# P-FTINT-1-1.net
KiCad netlist of a schematic drawn in Altium Designer
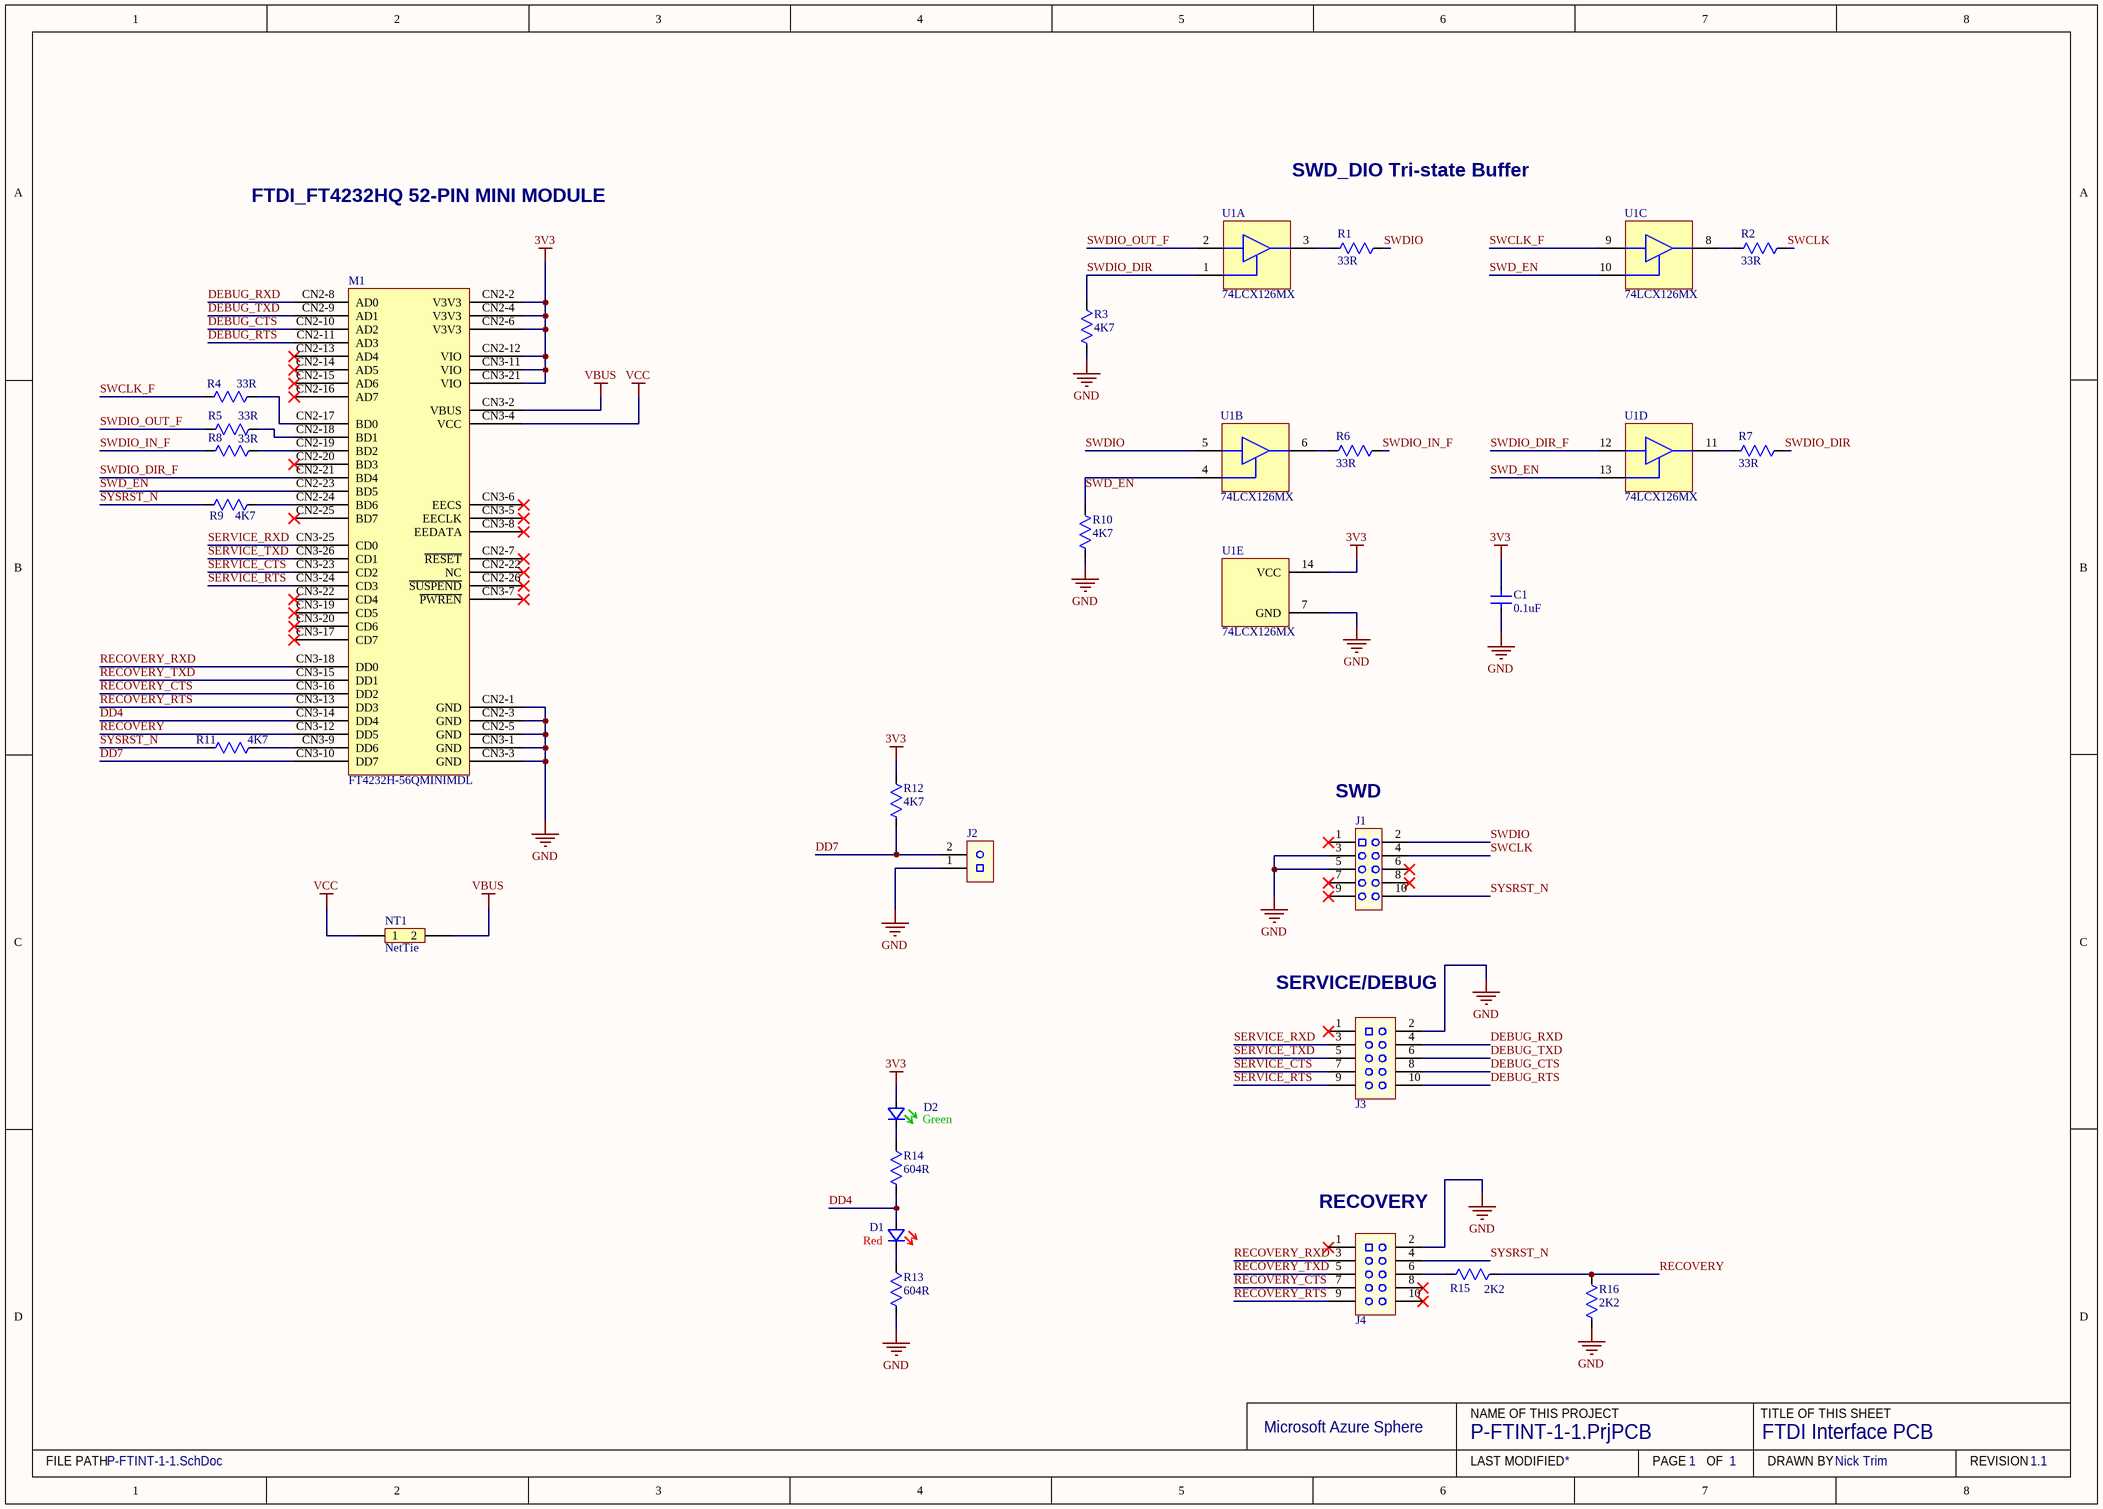
[diagram p0: P-FTINT-1-1.SchDoc]

(export (version "E")
  (design (tool "Eeschema 10.0.6"))
  (components
    (comp (ref "C1")
      (value "0.1uF")
      (footprint "CAP 0603 (1608) x 1.2mm")
      (description "CAP CER 0.1UF 25V X7R 0603")
      (fields
        (field (name "MANUFACTURER") "TDK")
        (field (name "MANUFACTURER PART NUMBER") "CGA3E2X7R1E104K080AA")
      )
      (libsource (lib "TDK-Capacitor_C_0603") (part "CGA3E2X7R1E104K080AA"))
    )
    (comp (ref "D1")
      (value "SML-D12U")
      (footprint "Rohm SML-D12 Red")
      (description "1.6 x 0.8 x 0.55mm (0603) LED 620nm Red")
      (fields
        (field (name "MANUFACTURER") "Rohm Semiconductor")
        (field (name "MANUFACTURER PART NUMBER") "SML-D12U8WT86")
        (field (name "COLOUR") "Red")
      )
      (libsource (lib "Rohm") (part "SML-D12U"))
    )
    (comp (ref "D2")
      (value "SML-D12P")
      (footprint "Rohm SML-D12 Green")
      (description "1.6 x 0.8 x 0.55mm (0603) LED 560nm Green")
      (fields
        (field (name "MANUFACTURER") "Rohm Semiconductor")
        (field (name "MANUFACTURER PART NUMBER") "SML-D12P8WT86")
        (field (name "COLOUR") "Green")
      )
      (libsource (lib "Rohm") (part "SML-D12P"))
    )
    (comp (ref "J1")
      (value "FTSH-105-01-F-DV-K")
      (footprint "SAMTEC-FTSH-105-01-X-DV-K")
      (description "CONN HEADER 10POS DUAL .05\" SMD")
      (fields (field (name "MANUFACTURER") "Samtec Inc."))
      (libsource (lib "Samtec") (part "FTSH-105-01-F-DV-K"))
    )
    (comp (ref "J2")
      (value "MOLEX-0022284020")
      (footprint "0022284020")
      (description "CONN HEADER 2POS .100 VERT TIN")
      (fields
        (field (name "MANUFACTURER") "Molex, LLC")
        (field (name "MANUFACTURER PART NUMBER") "0022284020")
      )
      (libsource (lib "Molex") (part "MOLEX-0022284020"))
    )
    (comp (ref "J3")
      (value "0901310765")
      (footprint "901310765")
      (description "CONN HEADER 10POS .100\" STR GOLD")
      (fields (field (name "MANUFACTURER") "Molex, LLC"))
      (libsource (lib "Molex") (part "MOLEX-0901310765"))
    )
    (comp (ref "J4")
      (value "0901310765")
      (footprint "901310765")
      (description "CONN HEADER 10POS .100\" STR GOLD")
      (fields (field (name "MANUFACTURER") "Molex, LLC"))
      (libsource (lib "Molex") (part "MOLEX-0901310765"))
    )
    (comp (ref "M1")
      (value "FT4232H-56QMINIMDL")
      (footprint "FT4232H-56Q")
      (description "IC MINI MODULE USB/FIFO 56QFN")
      (fields (field (name "MANUFACTURER") "FTDI"))
      (libsource (lib "FTDI") (part "FT4232H-56QMINIMDL"))
    )
    (comp (ref "NT1") (value "NetTie") (footprint "NetTie") (libsource (lib "generic") (part "NetTie")))
    (comp (ref "R1")
      (value "33R")
      (footprint "RES0603")
      (description "RES SMD 33 OHM 5% 1/10W 0603")
      (fields
        (field (name "MANUFACTURER") "Panasonic")
        (field (name "MANUFACTURER PART NUMBER") "ERJ-3GEYJ330V")
      )
      (libsource (lib "Panasonic_Resistor_ERJ3GR_0603") (part "ERJ-3GEYJ330V"))
    )
    (comp (ref "R2")
      (value "33R")
      (footprint "RES0603")
      (description "RES SMD 33 OHM 5% 1/10W 0603")
      (fields
        (field (name "MANUFACTURER") "Panasonic")
        (field (name "MANUFACTURER PART NUMBER") "ERJ-3GEYJ330V")
      )
      (libsource (lib "Panasonic_Resistor_ERJ3GR_0603") (part "ERJ-3GEYJ330V"))
    )
    (comp (ref "R3")
      (value "4K7")
      (footprint "RES0603")
      (description "RES SMD 4.7K OHM 5% 1/10W 0603")
      (fields
        (field (name "MANUFACTURER") "Panasonic")
        (field (name "MANUFACTURER PART NUMBER") "ERJ-3GEYJ472V")
      )
      (libsource (lib "Panasonic_Resistor_ERJ3GR_0603") (part "ERJ-3GEYJ472V"))
    )
    (comp (ref "R4")
      (value "33R")
      (footprint "RES0603")
      (description "RES SMD 33 OHM 5% 1/10W 0603")
      (fields
        (field (name "MANUFACTURER") "Panasonic")
        (field (name "MANUFACTURER PART NUMBER") "ERJ-3GEYJ330V")
      )
      (libsource (lib "Panasonic_Resistor_ERJ3GR_0603") (part "ERJ-3GEYJ330V"))
    )
    (comp (ref "R5")
      (value "33R")
      (footprint "RES0603")
      (description "RES SMD 33 OHM 5% 1/10W 0603")
      (fields
        (field (name "MANUFACTURER") "Panasonic")
        (field (name "MANUFACTURER PART NUMBER") "ERJ-3GEYJ330V")
      )
      (libsource (lib "Panasonic_Resistor_ERJ3GR_0603") (part "ERJ-3GEYJ330V"))
    )
    (comp (ref "R6")
      (value "33R")
      (footprint "RES0603")
      (description "RES SMD 33 OHM 5% 1/10W 0603")
      (fields
        (field (name "MANUFACTURER") "Panasonic")
        (field (name "MANUFACTURER PART NUMBER") "ERJ-3GEYJ330V")
      )
      (libsource (lib "Panasonic_Resistor_ERJ3GR_0603") (part "ERJ-3GEYJ330V"))
    )
    (comp (ref "R7")
      (value "33R")
      (footprint "RES0603")
      (description "RES SMD 33 OHM 5% 1/10W 0603")
      (fields
        (field (name "MANUFACTURER") "Panasonic")
        (field (name "MANUFACTURER PART NUMBER") "ERJ-3GEYJ330V")
      )
      (libsource (lib "Panasonic_Resistor_ERJ3GR_0603") (part "ERJ-3GEYJ330V"))
    )
    (comp (ref "R8")
      (value "33R")
      (footprint "RES0603")
      (description "RES SMD 33 OHM 5% 1/10W 0603")
      (fields
        (field (name "MANUFACTURER") "Panasonic")
        (field (name "MANUFACTURER PART NUMBER") "ERJ-3GEYJ330V")
      )
      (libsource (lib "Panasonic_Resistor_ERJ3GR_0603") (part "ERJ-3GEYJ330V"))
    )
    (comp (ref "R9")
      (value "4K7")
      (footprint "RES0603")
      (description "RES SMD 4.7K OHM 5% 1/10W 0603")
      (fields
        (field (name "MANUFACTURER") "Panasonic")
        (field (name "MANUFACTURER PART NUMBER") "ERJ-3GEYJ472V")
      )
      (libsource (lib "Panasonic_Resistor_ERJ3GR_0603") (part "ERJ-3GEYJ472V"))
    )
    (comp (ref "R10")
      (value "4K7")
      (footprint "RES0603")
      (description "RES SMD 4.7K OHM 5% 1/10W 0603")
      (fields
        (field (name "MANUFACTURER") "Panasonic")
        (field (name "MANUFACTURER PART NUMBER") "ERJ-3GEYJ472V")
      )
      (libsource (lib "Panasonic_Resistor_ERJ3GR_0603") (part "ERJ-3GEYJ472V"))
    )
    (comp (ref "R11")
      (value "4K7")
      (footprint "RES0603")
      (description "RES SMD 4.7K OHM 5% 1/10W 0603")
      (fields
        (field (name "MANUFACTURER") "Panasonic")
        (field (name "MANUFACTURER PART NUMBER") "ERJ-3GEYJ472V")
      )
      (libsource (lib "Panasonic_Resistor_ERJ3GR_0603") (part "ERJ-3GEYJ472V"))
    )
    (comp (ref "R12")
      (value "4K7")
      (footprint "RES0603")
      (description "RES SMD 4.7K OHM 5% 1/10W 0603")
      (fields
        (field (name "MANUFACTURER") "Panasonic")
        (field (name "MANUFACTURER PART NUMBER") "ERJ-3GEYJ472V")
      )
      (libsource (lib "Panasonic_Resistor_ERJ3GR_0603") (part "ERJ-3GEYJ472V"))
    )
    (comp (ref "R13")
      (value "604R")
      (footprint "RES0603")
      (description "RES SMD 604 OHM 1% 1/10W 0603")
      (fields
        (field (name "MANUFACTURER") "Panasonic")
        (field (name "MANUFACTURER PART NUMBER") "ERJ-3EKF6040V")
      )
      (libsource (lib "Panasonic_Resistor_ERJ3GR_0603") (part "ERJ-3EKF6040V"))
    )
    (comp (ref "R14")
      (value "604R")
      (footprint "RES0603")
      (description "RES SMD 604 OHM 1% 1/10W 0603")
      (fields
        (field (name "MANUFACTURER") "Panasonic")
        (field (name "MANUFACTURER PART NUMBER") "ERJ-3EKF6040V")
      )
      (libsource (lib "Panasonic_Resistor_ERJ3GR_0603") (part "ERJ-3EKF6040V"))
    )
    (comp (ref "R15")
      (value "2K2")
      (footprint "RES0603")
      (description "RES SMD 2.2K OHM 5% 1/10W 0603")
      (fields
        (field (name "MANUFACTURER") "Panasonic")
        (field (name "MANUFACTURER PART NUMBER") "ERJ-3GEYJ222V")
      )
      (libsource (lib "Panasonic_Resistor_ERJ3GR_0603") (part "ERJ-3GEYJ222V"))
    )
    (comp (ref "R16")
      (value "2K2")
      (footprint "RES0603")
      (description "RES SMD 2.2K OHM 5% 1/10W 0603")
      (fields
        (field (name "MANUFACTURER") "Panasonic")
        (field (name "MANUFACTURER PART NUMBER") "ERJ-3GEYJ222V")
      )
      (libsource (lib "Panasonic_Resistor_ERJ3GR_0603") (part "ERJ-3GEYJ222V"))
    )
    (comp (ref "U1")
      (value "74LCX126MX")
      (footprint "74LCX126MX")
      (description "Buffers & Line Drivers LV Quad Buffer 5V Tolerant I/O")
      (fields (field (name "MANUFACTURER") "ON Semiconductor / Fairchild"))
      (libsource (lib "OnSemiconductor") (part "74LCX126MX"))
    )
  )
  (nets
    (net (code "1") (name "/DD4") (class "Default")
      (node (ref "D1") (pin "2") (pinfunction "A_2") (pintype "passive"))
      (node (ref "M1") (pin "CN3-14") (pinfunction "DD4_CN3-14") (pintype "passive"))
      (node (ref "R14") (pin "2") (pinfunction "2_2") (pintype "passive"))
    )
    (net (code "2") (name "/DD7") (class "Default")
      (node (ref "J2") (pin "2") (pinfunction "2_2") (pintype "passive"))
      (node (ref "M1") (pin "CN3-10") (pinfunction "DD7_CN3-10") (pintype "passive"))
      (node (ref "R12") (pin "2") (pinfunction "2_2") (pintype "passive"))
    )
    (net (code "3") (name "/DEBUG_CTS") (class "Default")
      (node (ref "J3") (pin "8") (pinfunction "8_8") (pintype "passive"))
      (node (ref "M1") (pin "CN2-10") (pinfunction "AD2_CN2-10") (pintype "passive"))
    )
    (net (code "4") (name "/DEBUG_RTS") (class "Default")
      (node (ref "J3") (pin "10") (pinfunction "10_10") (pintype "passive"))
      (node (ref "M1") (pin "CN2-11") (pinfunction "AD3_CN2-11") (pintype "passive"))
    )
    (net (code "5") (name "/DEBUG_RXD") (class "Default")
      (node (ref "J3") (pin "4") (pinfunction "4_4") (pintype "passive"))
      (node (ref "M1") (pin "CN2-8") (pinfunction "AD0_CN2-8") (pintype "passive"))
    )
    (net (code "6") (name "/DEBUG_TXD") (class "Default")
      (node (ref "J3") (pin "6") (pinfunction "6_6") (pintype "passive"))
      (node (ref "M1") (pin "CN2-9") (pinfunction "AD1_CN2-9") (pintype "passive"))
    )
    (net (code "7") (name "/RECOVERY") (class "Default")
      (node (ref "M1") (pin "CN3-12") (pinfunction "DD5_CN3-12") (pintype "passive"))
      (node (ref "R15") (pin "1") (pinfunction "1_1") (pintype "passive"))
      (node (ref "R16") (pin "1") (pinfunction "1_1") (pintype "passive"))
    )
    (net (code "8") (name "/RECOVERY_CTS") (class "Default")
      (node (ref "J4") (pin "7") (pinfunction "7_7") (pintype "passive"))
      (node (ref "M1") (pin "CN3-16") (pinfunction "DD2_CN3-16") (pintype "passive"))
    )
    (net (code "9") (name "/RECOVERY_RTS") (class "Default")
      (node (ref "J4") (pin "9") (pinfunction "9_9") (pintype "passive"))
      (node (ref "M1") (pin "CN3-13") (pinfunction "DD3_CN3-13") (pintype "passive"))
    )
    (net (code "10") (name "/RECOVERY_RXD") (class "Default")
      (node (ref "J4") (pin "3") (pinfunction "3_3") (pintype "passive"))
      (node (ref "M1") (pin "CN3-18") (pinfunction "DD0_CN3-18") (pintype "passive"))
    )
    (net (code "11") (name "/RECOVERY_TXD") (class "Default")
      (node (ref "J4") (pin "5") (pinfunction "5_5") (pintype "passive"))
      (node (ref "M1") (pin "CN3-15") (pinfunction "DD1_CN3-15") (pintype "passive"))
    )
    (net (code "12") (name "/SERVICE_CTS") (class "Default")
      (node (ref "J3") (pin "7") (pinfunction "7_7") (pintype "passive"))
      (node (ref "M1") (pin "CN3-23") (pinfunction "CD2_CN3-23") (pintype "passive"))
    )
    (net (code "13") (name "/SERVICE_RTS") (class "Default")
      (node (ref "J3") (pin "9") (pinfunction "9_9") (pintype "passive"))
      (node (ref "M1") (pin "CN3-24") (pinfunction "CD3_CN3-24") (pintype "passive"))
    )
    (net (code "14") (name "/SERVICE_RXD") (class "Default")
      (node (ref "J3") (pin "3") (pinfunction "3_3") (pintype "passive"))
      (node (ref "M1") (pin "CN3-25") (pinfunction "CD0_CN3-25") (pintype "passive"))
    )
    (net (code "15") (name "/SERVICE_TXD") (class "Default")
      (node (ref "J3") (pin "5") (pinfunction "5_5") (pintype "passive"))
      (node (ref "M1") (pin "CN3-26") (pinfunction "CD1_CN3-26") (pintype "passive"))
    )
    (net (code "16") (name "/SWCLK") (class "Default")
      (node (ref "J1") (pin "4") (pinfunction "4_4") (pintype "passive"))
      (node (ref "R2") (pin "1") (pinfunction "1_1") (pintype "passive"))
    )
    (net (code "17") (name "/SWCLK_F") (class "Default")
      (node (ref "R4") (pin "2") (pinfunction "2_2") (pintype "passive"))
      (node (ref "U1") (pin "9") (pinfunction "3A_9") (pintype "passive"))
    )
    (net (code "18") (name "/SWDIO") (class "Default")
      (node (ref "J1") (pin "2") (pinfunction "2_2") (pintype "passive"))
      (node (ref "R1") (pin "1") (pinfunction "1_1") (pintype "passive"))
      (node (ref "U1") (pin "5") (pinfunction "2A_5") (pintype "passive"))
    )
    (net (code "19") (name "/SWDIO_DIR") (class "Default")
      (node (ref "R3") (pin "1") (pinfunction "1_1") (pintype "passive"))
      (node (ref "R7") (pin "1") (pinfunction "1_1") (pintype "passive"))
      (node (ref "U1") (pin "1") (pinfunction "1OE_1") (pintype "passive"))
    )
    (net (code "20") (name "/SWDIO_DIR_F") (class "Default")
      (node (ref "M1") (pin "CN2-21") (pinfunction "BD4_CN2-21") (pintype "passive"))
      (node (ref "U1") (pin "12") (pinfunction "4A_12") (pintype "passive"))
    )
    (net (code "21") (name "/SWDIO_IN_F") (class "Default")
      (node (ref "R6") (pin "1") (pinfunction "1_1") (pintype "passive"))
      (node (ref "R8") (pin "2") (pinfunction "2_2") (pintype "passive"))
    )
    (net (code "22") (name "/SWDIO_OUT_F") (class "Default")
      (node (ref "R5") (pin "2") (pinfunction "2_2") (pintype "passive"))
      (node (ref "U1") (pin "2") (pinfunction "1A_2") (pintype "passive"))
    )
    (net (code "23") (name "/SWD_EN") (class "Default")
      (node (ref "M1") (pin "CN2-23") (pinfunction "BD5_CN2-23") (pintype "passive"))
      (node (ref "R10") (pin "1") (pinfunction "1_1") (pintype "passive"))
      (node (ref "U1") (pin "10") (pinfunction "3OE_10") (pintype "passive"))
      (node (ref "U1") (pin "13") (pinfunction "4OE_13") (pintype "passive"))
      (node (ref "U1") (pin "4") (pinfunction "2OE_4") (pintype "passive"))
    )
    (net (code "24") (name "/SYSRST_N") (class "Default")
      (node (ref "J1") (pin "10") (pinfunction "10_10") (pintype "passive"))
      (node (ref "J4") (pin "4") (pinfunction "4_4") (pintype "passive"))
      (node (ref "R11") (pin "2") (pinfunction "2_2") (pintype "passive"))
      (node (ref "R9") (pin "2") (pinfunction "2_2") (pintype "passive"))
    )
    (net (code "25") (name "3V3") (class "Default")
      (node (ref "C1") (pin "2") (pinfunction "2_2") (pintype "passive"))
      (node (ref "D2") (pin "2") (pinfunction "A_2") (pintype "passive"))
      (node (ref "M1") (pin "CN2-12") (pinfunction "VIO_CN2-12") (pintype "passive"))
      (node (ref "M1") (pin "CN2-2") (pinfunction "V3V3_CN2-2") (pintype "passive"))
      (node (ref "M1") (pin "CN2-4") (pinfunction "V3V3_CN2-4") (pintype "passive"))
      (node (ref "M1") (pin "CN2-6") (pinfunction "V3V3_CN2-6") (pintype "passive"))
      (node (ref "M1") (pin "CN3-11") (pinfunction "VIO_CN3-11") (pintype "passive"))
      (node (ref "M1") (pin "CN3-21") (pinfunction "VIO_CN3-21") (pintype "passive"))
      (node (ref "R12") (pin "1") (pinfunction "1_1") (pintype "passive"))
      (node (ref "U1") (pin "14") (pinfunction "VCC_14") (pintype "passive"))
    )
    (net (code "26") (name "GND") (class "Default")
      (node (ref "C1") (pin "1") (pinfunction "1_1") (pintype "passive"))
      (node (ref "J1") (pin "3") (pinfunction "3_3") (pintype "passive"))
      (node (ref "J1") (pin "5") (pinfunction "5_5") (pintype "passive"))
      (node (ref "J2") (pin "1") (pinfunction "1_1") (pintype "passive"))
      (node (ref "J3") (pin "2") (pinfunction "2_2") (pintype "passive"))
      (node (ref "J4") (pin "2") (pinfunction "2_2") (pintype "passive"))
      (node (ref "M1") (pin "CN2-1") (pinfunction "GND_CN2-1") (pintype "passive"))
      (node (ref "M1") (pin "CN2-3") (pinfunction "GND_CN2-3") (pintype "passive"))
      (node (ref "M1") (pin "CN2-5") (pinfunction "GND_CN2-5") (pintype "passive"))
      (node (ref "M1") (pin "CN3-1") (pinfunction "GND_CN3-1") (pintype "passive"))
      (node (ref "M1") (pin "CN3-3") (pinfunction "GND_CN3-3") (pintype "passive"))
      (node (ref "R10") (pin "2") (pinfunction "2_2") (pintype "passive"))
      (node (ref "R13") (pin "2") (pinfunction "2_2") (pintype "passive"))
      (node (ref "R16") (pin "2") (pinfunction "2_2") (pintype "passive"))
      (node (ref "R3") (pin "2") (pinfunction "2_2") (pintype "passive"))
      (node (ref "U1") (pin "7") (pinfunction "GND_7") (pintype "power_in"))
    )
    (net (code "27") (name "Net-(D1-K)") (class "Default")
      (node (ref "D1") (pin "1") (pinfunction "K_1") (pintype "passive"))
      (node (ref "R13") (pin "1") (pinfunction "1_1") (pintype "passive"))
    )
    (net (code "28") (name "Net-(D2-K)") (class "Default")
      (node (ref "D2") (pin "1") (pinfunction "K_1") (pintype "passive"))
      (node (ref "R14") (pin "1") (pinfunction "1_1") (pintype "passive"))
    )
    (net (code "29") (name "Net-(J4-Pad6)") (class "Default")
      (node (ref "J4") (pin "6") (pinfunction "6_6") (pintype "passive"))
      (node (ref "R15") (pin "2") (pinfunction "2_2") (pintype "passive"))
    )
    (net (code "30") (name "Net-(M1-BD0)") (class "Default")
      (node (ref "M1") (pin "CN2-17") (pinfunction "BD0_CN2-17") (pintype "passive"))
      (node (ref "R4") (pin "1") (pinfunction "1_1") (pintype "passive"))
    )
    (net (code "31") (name "Net-(M1-BD1)") (class "Default")
      (node (ref "M1") (pin "CN2-18") (pinfunction "BD1_CN2-18") (pintype "passive"))
      (node (ref "R5") (pin "1") (pinfunction "1_1") (pintype "passive"))
    )
    (net (code "32") (name "Net-(M1-BD2)") (class "Default")
      (node (ref "M1") (pin "CN2-19") (pinfunction "BD2_CN2-19") (pintype "passive"))
      (node (ref "R8") (pin "1") (pinfunction "1_1") (pintype "passive"))
    )
    (net (code "33") (name "Net-(M1-BD6)") (class "Default")
      (node (ref "M1") (pin "CN2-24") (pinfunction "BD6_CN2-24") (pintype "passive"))
      (node (ref "R9") (pin "1") (pinfunction "1_1") (pintype "passive"))
    )
    (net (code "34") (name "Net-(M1-DD6)") (class "Default")
      (node (ref "M1") (pin "CN3-9") (pinfunction "DD6_CN3-9") (pintype "passive"))
      (node (ref "R11") (pin "1") (pinfunction "1_1") (pintype "passive"))
    )
    (net (code "35") (name "Net-(U1A-1Y)") (class "Default")
      (node (ref "R1") (pin "2") (pinfunction "2_2") (pintype "passive"))
      (node (ref "U1") (pin "3") (pinfunction "1Y_3") (pintype "passive"))
    )
    (net (code "36") (name "Net-(U1B-2Y)") (class "Default")
      (node (ref "R6") (pin "2") (pinfunction "2_2") (pintype "passive"))
      (node (ref "U1") (pin "6") (pinfunction "2Y_6") (pintype "passive"))
    )
    (net (code "37") (name "Net-(U1C-3Y)") (class "Default")
      (node (ref "R2") (pin "2") (pinfunction "2_2") (pintype "passive"))
      (node (ref "U1") (pin "8") (pinfunction "3Y_8") (pintype "passive"))
    )
    (net (code "38") (name "Net-(U1D-4Y)") (class "Default")
      (node (ref "R7") (pin "2") (pinfunction "2_2") (pintype "passive"))
      (node (ref "U1") (pin "11") (pinfunction "4Y_11") (pintype "passive"))
    )
    (net (code "39") (name "VBUS") (class "Default")
      (node (ref "M1") (pin "CN3-2") (pinfunction "VBUS_CN3-2") (pintype "passive"))
      (node (ref "NT1") (pin "2") (pinfunction "2_2") (pintype "passive"))
    )
    (net (code "40") (name "VCC") (class "Default")
      (node (ref "M1") (pin "CN3-4") (pinfunction "VCC_CN3-4") (pintype "passive"))
      (node (ref "NT1") (pin "1") (pinfunction "1_1") (pintype "passive"))
    )
    (net (code "41") (name "unconnected-(J1-Pad1)") (class "Default")
      (node (ref "J1") (pin "1") (pinfunction "1_1") (pintype "passive+no_connect"))
    )
    (net (code "42") (name "unconnected-(J1-Pad6)") (class "Default")
      (node (ref "J1") (pin "6") (pinfunction "6_6") (pintype "passive+no_connect"))
    )
    (net (code "43") (name "unconnected-(J1-Pad7)") (class "Default")
      (node (ref "J1") (pin "7") (pinfunction "7_7") (pintype "passive+no_connect"))
    )
    (net (code "44") (name "unconnected-(J1-Pad8)") (class "Default")
      (node (ref "J1") (pin "8") (pinfunction "8_8") (pintype "passive+no_connect"))
    )
    (net (code "45") (name "unconnected-(J1-Pad9)") (class "Default")
      (node (ref "J1") (pin "9") (pinfunction "9_9") (pintype "passive+no_connect"))
    )
    (net (code "46") (name "unconnected-(J3-Pad1)") (class "Default")
      (node (ref "J3") (pin "1") (pinfunction "1_1") (pintype "passive+no_connect"))
    )
    (net (code "47") (name "unconnected-(J4-Pad1)") (class "Default")
      (node (ref "J4") (pin "1") (pinfunction "1_1") (pintype "passive+no_connect"))
    )
    (net (code "48") (name "unconnected-(J4-Pad8)") (class "Default")
      (node (ref "J4") (pin "8") (pinfunction "8_8") (pintype "passive+no_connect"))
    )
    (net (code "49") (name "unconnected-(J4-Pad10)") (class "Default")
      (node (ref "J4") (pin "10") (pinfunction "10_10") (pintype "passive+no_connect"))
    )
    (net (code "50") (name "unconnected-(M1-AD4-PadCN2-13)") (class "Default")
      (node (ref "M1") (pin "CN2-13") (pinfunction "AD4_CN2-13") (pintype "passive+no_connect"))
    )
    (net (code "51") (name "unconnected-(M1-AD5-PadCN2-14)") (class "Default")
      (node (ref "M1") (pin "CN2-14") (pinfunction "AD5_CN2-14") (pintype "passive+no_connect"))
    )
    (net (code "52") (name "unconnected-(M1-AD6-PadCN2-15)") (class "Default")
      (node (ref "M1") (pin "CN2-15") (pinfunction "AD6_CN2-15") (pintype "passive+no_connect"))
    )
    (net (code "53") (name "unconnected-(M1-AD7-PadCN2-16)") (class "Default")
      (node (ref "M1") (pin "CN2-16") (pinfunction "AD7_CN2-16") (pintype "passive+no_connect"))
    )
    (net (code "54") (name "unconnected-(M1-BD3-PadCN2-20)") (class "Default")
      (node (ref "M1") (pin "CN2-20") (pinfunction "BD3_CN2-20") (pintype "passive+no_connect"))
    )
    (net (code "55") (name "unconnected-(M1-BD7-PadCN2-25)") (class "Default")
      (node (ref "M1") (pin "CN2-25") (pinfunction "BD7_CN2-25") (pintype "passive+no_connect"))
    )
    (net (code "56") (name "unconnected-(M1-CD4-PadCN3-22)") (class "Default")
      (node (ref "M1") (pin "CN3-22") (pinfunction "CD4_CN3-22") (pintype "passive+no_connect"))
    )
    (net (code "57") (name "unconnected-(M1-CD5-PadCN3-19)") (class "Default")
      (node (ref "M1") (pin "CN3-19") (pinfunction "CD5_CN3-19") (pintype "passive+no_connect"))
    )
    (net (code "58") (name "unconnected-(M1-CD6-PadCN3-20)") (class "Default")
      (node (ref "M1") (pin "CN3-20") (pinfunction "CD6_CN3-20") (pintype "passive+no_connect"))
    )
    (net (code "59") (name "unconnected-(M1-CD7-PadCN3-17)") (class "Default")
      (node (ref "M1") (pin "CN3-17") (pinfunction "CD7_CN3-17") (pintype "passive+no_connect"))
    )
    (net (code "60") (name "unconnected-(M1-EECLK-PadCN3-5)") (class "Default")
      (node (ref "M1") (pin "CN3-5") (pinfunction "EECLK_CN3-5") (pintype "passive+no_connect"))
    )
    (net (code "61") (name "unconnected-(M1-EECS-PadCN3-6)") (class "Default")
      (node (ref "M1") (pin "CN3-6") (pinfunction "EECS_CN3-6") (pintype "passive+no_connect"))
    )
    (net (code "62") (name "unconnected-(M1-EEDATA-PadCN3-8)") (class "Default")
      (node (ref "M1") (pin "CN3-8") (pinfunction "EEDATA_CN3-8") (pintype "passive+no_connect"))
    )
    (net (code "63") (name "unconnected-(M1-NC-PadCN2-22)") (class "Default")
      (node (ref "M1") (pin "CN2-22") (pinfunction "NC_CN2-22") (pintype "passive+no_connect"))
    )
    (net (code "64") (name "unconnected-(M1-~{PWREN}-PadCN3-7)") (class "Default")
      (node (ref "M1") (pin "CN3-7") (pinfunction "~{PWREN}_CN3-7") (pintype "passive+no_connect"))
    )
    (net (code "65") (name "unconnected-(M1-~{RESET}-PadCN2-7)") (class "Default")
      (node (ref "M1") (pin "CN2-7") (pinfunction "~{RESET}_CN2-7") (pintype "passive+no_connect"))
    )
    (net (code "66") (name "unconnected-(M1-~{SUSPEND}-PadCN2-26)") (class "Default")
      (node (ref "M1") (pin "CN2-26") (pinfunction "~{SUSPEND}_CN2-26") (pintype "passive+no_connect"))
    )
  )
)
